# K10P100_V1_0.net
KiCad netlist of a schematic drawn in Altium Designer
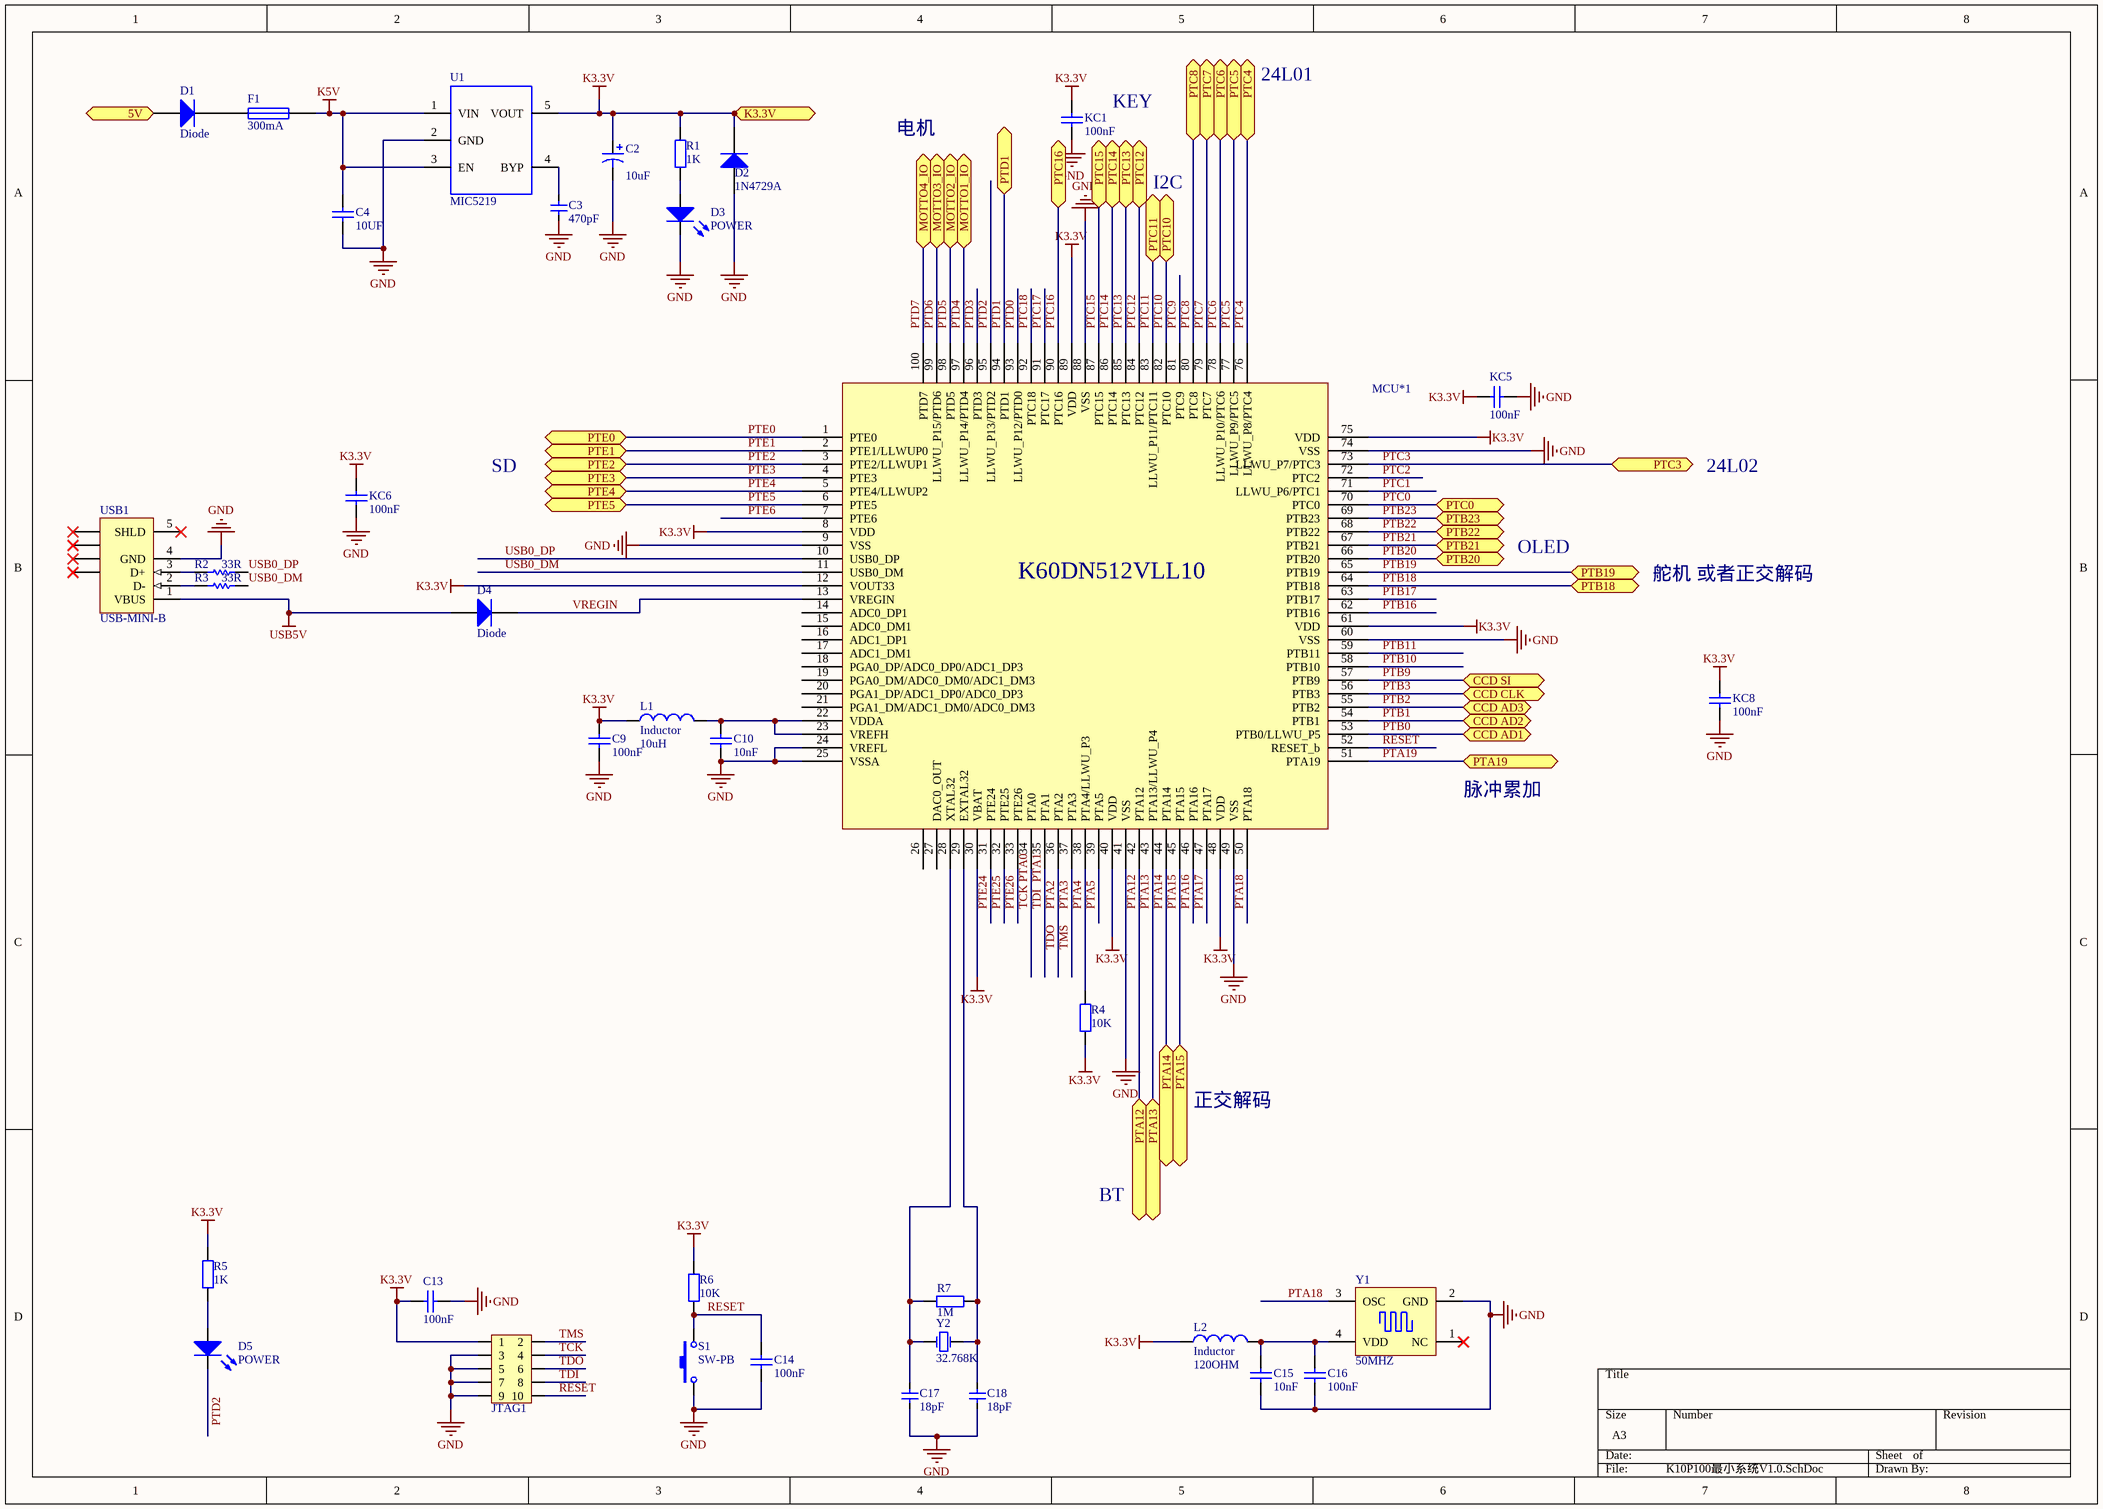
[diagram p0: K10P100最小系统V1.0.SchDoc]

(export (version "E")
  (design (tool "Eeschema 10.0.6"))
  (components
    (comp (ref "C2")
      (value "10uF")
      (footprint "C2012")
      (description "Polarized Capacitor (Radial)")
      (fields (field (name "Comment") "Cap Pol1") (field (name "PUBLISHER") "Altium Limited"))
      (libsource (lib "Miscellaneous Devices") (part "Cap Pol1"))
    )
    (comp (ref "C3")
      (value "470pF")
      (footprint "C2012")
      (description "CAP")
      (libsource (lib "K60-V4.0") (part "陶瓷电容"))
    )
    (comp (ref "C4")
      (value "10UF")
      (footprint "C2012")
      (description "Capacitor")
      (libsource (lib "K60-V4.0") (part "Cap"))
    )
    (comp (ref "C9")
      (value "100nF")
      (footprint "C2012")
      (description "Capacitor")
      (libsource (lib "K60-V4.0") (part "Cap"))
    )
    (comp (ref "C10")
      (value "10nF")
      (footprint "C2012")
      (description "Capacitor")
      (libsource (lib "K60-V4.0") (part "Cap"))
    )
    (comp (ref "C13")
      (value "100nF")
      (footprint "C2012")
      (description "Capacitor")
      (libsource (lib "K60-V4.0") (part "Cap"))
    )
    (comp (ref "C14")
      (value "100nF")
      (footprint "C2012")
      (description "Capacitor")
      (libsource (lib "K60-V4.0") (part "Cap"))
    )
    (comp (ref "C15")
      (value "10nF")
      (footprint "C2012")
      (description "Capacitor")
      (libsource (lib "K60-V4.0") (part "Cap"))
    )
    (comp (ref "C16")
      (value "100nF")
      (footprint "C2012")
      (description "Capacitor")
      (libsource (lib "K60-V4.0") (part "Cap"))
    )
    (comp (ref "C17")
      (value "18pF")
      (footprint "C2012")
      (description "CAP")
      (libsource (lib "K60-V4.0") (part "陶瓷电容"))
    )
    (comp (ref "C18")
      (value "18pF")
      (footprint "C2012")
      (description "CAP")
      (libsource (lib "K60-V4.0") (part "陶瓷电容"))
    )
    (comp (ref "D1")
      (value "Diode")
      (footprint "1206(2)")
      (description "Default Diode")
      (fields (field (name "PUBLISHER") "Altium Limited"))
      (libsource (lib "Miscellaneous Devices") (part "Diode"))
    )
    (comp (ref "D2")
      (value "1N4729A")
      (footprint "C2012")
      (description "High Conductance Fast Diode")
      (fields (field (name "PUBLISHER") "Altium Limited"))
      (libsource (lib "K60-V4.0") (part "Diode 1N4148"))
    )
    (comp (ref "D3")
      (value "POWER")
      (footprint "C2012")
      (description "Typical INFRARED GaAs LED")
      (libsource (lib "K60-V4.0") (part "LED"))
    )
    (comp (ref "D4")
      (value "Diode")
      (footprint "1206(2)")
      (description "Default Diode")
      (fields (field (name "PUBLISHER") "Altium Limited"))
      (libsource (lib "Miscellaneous Devices") (part "Diode"))
    )
    (comp (ref "D5")
      (value "POWER")
      (footprint "C2012")
      (description "Typical INFRARED GaAs LED")
      (libsource (lib "K60-V4.0") (part "LED"))
    )
    (comp (ref "F1")
      (value "300mA")
      (footprint "R2012")
      (description "Fuse")
      (fields (field (name "PUBLISHER") "Altium Limited"))
      (libsource (lib "K60-V4.0") (part "Fuse 1"))
    )
    (comp (ref "JTAG1")
      (value "Header 5X2")
      (footprint "IDC5X2")
      (description "Header, 5-Pin, Dual row")
      (libsource (lib "K60-V4.0") (part "Header 5X2"))
    )
    (comp (ref "KC1")
      (value "100nF")
      (footprint "C2012")
      (description "Capacitor")
      (libsource (lib "K60-V4.0") (part "Cap"))
    )
    (comp (ref "KC5")
      (value "100nF")
      (footprint "C2012")
      (description "Capacitor")
      (libsource (lib "K60-V4.0") (part "Cap"))
    )
    (comp (ref "KC6")
      (value "100nF")
      (footprint "C2012")
      (description "Capacitor")
      (libsource (lib "K60-V4.0") (part "Cap"))
    )
    (comp (ref "KC8")
      (value "100nF")
      (footprint "C2012")
      (description "Capacitor")
      (libsource (lib "K60-V4.0") (part "Cap"))
    )
    (comp (ref "L1")
      (value "Inductor")
      (footprint "C2012")
      (fields (field (name "ALTIUM_VALUE") "10uH") (field (name "PUBLISHER") "Altium Limited"))
      (libsource (lib "Miscellaneous Devices") (part "Inductor"))
    )
    (comp (ref "L2")
      (value "Inductor")
      (footprint "C2012")
      (fields (field (name "ALTIUM_VALUE") "120OHM") (field (name "PUBLISHER") "Altium Limited"))
      (libsource (lib "Miscellaneous Devices") (part "Inductor"))
    )
    (comp (ref "MCU*1") (value "k60P100") (footprint "LQFP100") (libsource (lib "原理图") (part "k60P100")))
    (comp (ref "R1")
      (value "1K")
      (footprint "R2012")
      (description "Resistor of led")
      (libsource (lib "") (part "Res_1"))
    )
    (comp (ref "R2")
      (value "33R")
      (footprint "R2012")
      (description "贴片电阻")
      (fields (field (name "PUBLISHER") "Altium Limited"))
      (libsource (lib "Sparks") (part "Res"))
    )
    (comp (ref "R3")
      (value "33R")
      (footprint "R2012")
      (description "贴片电阻")
      (fields (field (name "PUBLISHER") "Altium Limited"))
      (libsource (lib "Sparks") (part "Res"))
    )
    (comp (ref "R4")
      (value "10K")
      (footprint "R2012")
      (description "Resistor of led")
      (libsource (lib "") (part "Res_1"))
    )
    (comp (ref "R5")
      (value "1K")
      (footprint "R2012")
      (description "Resistor of led")
      (libsource (lib "") (part "Res_1"))
    )
    (comp (ref "R6")
      (value "10K")
      (footprint "R2012")
      (description "Resistor")
      (libsource (lib "") (part "Res_1"))
    )
    (comp (ref "R7")
      (value "1M")
      (footprint "R2012")
      (description "Resistor")
      (libsource (lib "K60-V4.0") (part "Res"))
    )
    (comp (ref "S1")
      (value "SW-PB")
      (footprint "sw 3*4 *2")
      (description "Switch")
      (libsource (lib "K60-V4.0") (part "SW-PB"))
    )
    (comp (ref "U1")
      (value "MIC5219")
      (footprint "SOT-23-5")
      (description "LDO")
      (libsource (lib "K60-V4.0") (part "MIC5219"))
    )
    (comp (ref "USB1")
      (value "USB-MINI-B")
      (footprint "USB-MINI-B")
      (description "USB 2.0, Right Angle, SMT, A Type, Receptacle, 5 Position, Black")
      (fields (field (name "PUBLISHER") "Altium Limited"))
      (libsource (lib "Sparks") (part "USB-MINI-B"))
    )
    (comp (ref "Y1") (value "50MHZ") (footprint "贴片有源晶体") (libsource (lib "K60-V4.0") (part "XTAL1")))
    (comp (ref "Y2")
      (value "32.768K")
      (footprint "CT3215")
      (description "Crystal Oscillator")
      (libsource (lib "K60-V4.0") (part "XTAL"))
    )
  )
  (nets
    (net (code "1") (name "/5V") (class "Default")
      (node (ref "D1") (pin "1") (pinfunction "A_1") (pintype "passive"))
    )
    (net (code "2") (name "/PTA0") (class "Default")
      (node (ref "JTAG1") (pin "4") (pinfunction "4_4") (pintype "passive"))
      (node (ref "MCU*1") (pin "34") (pinfunction "PTA0_34") (pintype "passive"))
    )
    (net (code "3") (name "/PTA1") (class "Default")
      (node (ref "JTAG1") (pin "8") (pinfunction "8_8") (pintype "passive"))
      (node (ref "MCU*1") (pin "35") (pinfunction "PTA1_35") (pintype "passive"))
    )
    (net (code "4") (name "/PTA2") (class "Default")
      (node (ref "JTAG1") (pin "6") (pinfunction "6_6") (pintype "passive"))
      (node (ref "MCU*1") (pin "36") (pinfunction "PTA2_36") (pintype "passive"))
    )
    (net (code "5") (name "/PTA3") (class "Default")
      (node (ref "JTAG1") (pin "2") (pinfunction "2_2") (pintype "passive"))
      (node (ref "MCU*1") (pin "37") (pinfunction "PTA3_37") (pintype "passive"))
    )
    (net (code "6") (name "/PTA4") (class "Default")
      (node (ref "MCU*1") (pin "38") (pinfunction "PTA4/LLWU_P3_38") (pintype "passive"))
      (node (ref "R4") (pin "2") (pinfunction "2_2") (pintype "passive"))
    )
    (net (code "7") (name "/PTA5") (class "Default")
      (node (ref "MCU*1") (pin "39") (pinfunction "PTA5_39") (pintype "passive"))
    )
    (net (code "8") (name "/PTA12") (class "Default")
      (node (ref "MCU*1") (pin "42") (pinfunction "PTA12_42") (pintype "passive"))
    )
    (net (code "9") (name "/PTA13") (class "Default")
      (node (ref "MCU*1") (pin "43") (pinfunction "PTA13/LLWU_P4_43") (pintype "passive"))
    )
    (net (code "10") (name "/PTA14") (class "Default")
      (node (ref "MCU*1") (pin "44") (pinfunction "PTA14_44") (pintype "passive"))
    )
    (net (code "11") (name "/PTA15") (class "Default")
      (node (ref "MCU*1") (pin "45") (pinfunction "PTA15_45") (pintype "passive"))
    )
    (net (code "12") (name "/PTA16") (class "Default")
      (node (ref "MCU*1") (pin "46") (pinfunction "PTA16_46") (pintype "passive"))
    )
    (net (code "13") (name "/PTA17") (class "Default")
      (node (ref "MCU*1") (pin "47") (pinfunction "PTA17_47") (pintype "passive"))
    )
    (net (code "14") (name "/PTA18") (class "Default")
      (node (ref "MCU*1") (pin "50") (pinfunction "PTA18_50") (pintype "passive"))
      (node (ref "Y1") (pin "3") (pinfunction "OSC_3") (pintype "passive"))
    )
    (net (code "15") (name "/PTA19") (class "Default")
      (node (ref "MCU*1") (pin "51") (pinfunction "PTA19_51") (pintype "passive"))
    )
    (net (code "16") (name "/PTB0") (class "Default")
      (node (ref "MCU*1") (pin "53") (pinfunction "PTB0/LLWU_P5_53") (pintype "passive"))
    )
    (net (code "17") (name "/PTB1") (class "Default")
      (node (ref "MCU*1") (pin "54") (pinfunction "PTB1_54") (pintype "passive"))
    )
    (net (code "18") (name "/PTB2") (class "Default")
      (node (ref "MCU*1") (pin "55") (pinfunction "PTB2_55") (pintype "passive"))
    )
    (net (code "19") (name "/PTB3") (class "Default")
      (node (ref "MCU*1") (pin "56") (pinfunction "PTB3_56") (pintype "passive"))
    )
    (net (code "20") (name "/PTB9") (class "Default")
      (node (ref "MCU*1") (pin "57") (pinfunction "PTB9_57") (pintype "passive"))
    )
    (net (code "21") (name "/PTB10") (class "Default")
      (node (ref "MCU*1") (pin "58") (pinfunction "PTB10_58") (pintype "passive"))
    )
    (net (code "22") (name "/PTB11") (class "Default")
      (node (ref "MCU*1") (pin "59") (pinfunction "PTB11_59") (pintype "passive"))
    )
    (net (code "23") (name "/PTB16") (class "Default")
      (node (ref "MCU*1") (pin "62") (pinfunction "PTB16_62") (pintype "passive"))
    )
    (net (code "24") (name "/PTB17") (class "Default")
      (node (ref "MCU*1") (pin "63") (pinfunction "PTB17_63") (pintype "passive"))
    )
    (net (code "25") (name "/PTB18") (class "Default")
      (node (ref "MCU*1") (pin "64") (pinfunction "PTB18_64") (pintype "passive"))
    )
    (net (code "26") (name "/PTB19") (class "Default")
      (node (ref "MCU*1") (pin "65") (pinfunction "PTB19_65") (pintype "passive"))
    )
    (net (code "27") (name "/PTB20") (class "Default")
      (node (ref "MCU*1") (pin "66") (pinfunction "PTB20_66") (pintype "passive"))
    )
    (net (code "28") (name "/PTB21") (class "Default")
      (node (ref "MCU*1") (pin "67") (pinfunction "PTB21_67") (pintype "passive"))
    )
    (net (code "29") (name "/PTB22") (class "Default")
      (node (ref "MCU*1") (pin "68") (pinfunction "PTB22_68") (pintype "passive"))
    )
    (net (code "30") (name "/PTB23") (class "Default")
      (node (ref "MCU*1") (pin "69") (pinfunction "PTB23_69") (pintype "passive"))
    )
    (net (code "31") (name "/PTC0") (class "Default")
      (node (ref "MCU*1") (pin "70") (pinfunction "PTC0_70") (pintype "passive"))
    )
    (net (code "32") (name "/PTC1") (class "Default")
      (node (ref "MCU*1") (pin "71") (pinfunction "LLWU_P6/PTC1_71") (pintype "passive"))
    )
    (net (code "33") (name "/PTC2") (class "Default")
      (node (ref "MCU*1") (pin "72") (pinfunction "PTC2_72") (pintype "passive"))
    )
    (net (code "34") (name "/PTC3") (class "Default")
      (node (ref "MCU*1") (pin "73") (pinfunction "LLWU_P7/PTC3_73") (pintype "passive"))
    )
    (net (code "35") (name "/PTC4") (class "Default")
      (node (ref "MCU*1") (pin "76") (pinfunction "LLWU_P8/PTC4_76") (pintype "passive"))
    )
    (net (code "36") (name "/PTC5") (class "Default")
      (node (ref "MCU*1") (pin "77") (pinfunction "LLWU_P9/PTC5_77") (pintype "passive"))
    )
    (net (code "37") (name "/PTC6") (class "Default")
      (node (ref "MCU*1") (pin "78") (pinfunction "LLWU_P10/PTC6_78") (pintype "passive"))
    )
    (net (code "38") (name "/PTC7") (class "Default")
      (node (ref "MCU*1") (pin "79") (pinfunction "PTC7_79") (pintype "passive"))
    )
    (net (code "39") (name "/PTC8") (class "Default")
      (node (ref "MCU*1") (pin "80") (pinfunction "PTC8_80") (pintype "passive"))
    )
    (net (code "40") (name "/PTC9") (class "Default")
      (node (ref "MCU*1") (pin "81") (pinfunction "PTC9_81") (pintype "passive"))
    )
    (net (code "41") (name "/PTC10") (class "Default")
      (node (ref "MCU*1") (pin "82") (pinfunction "PTC10_82") (pintype "passive"))
    )
    (net (code "42") (name "/PTC11") (class "Default")
      (node (ref "MCU*1") (pin "83") (pinfunction "LLWU_P11/PTC11_83") (pintype "passive"))
    )
    (net (code "43") (name "/PTC12") (class "Default")
      (node (ref "MCU*1") (pin "84") (pinfunction "PTC12_84") (pintype "passive"))
    )
    (net (code "44") (name "/PTC13") (class "Default")
      (node (ref "MCU*1") (pin "85") (pinfunction "PTC13_85") (pintype "passive"))
    )
    (net (code "45") (name "/PTC14") (class "Default")
      (node (ref "MCU*1") (pin "86") (pinfunction "PTC14_86") (pintype "passive"))
    )
    (net (code "46") (name "/PTC15") (class "Default")
      (node (ref "MCU*1") (pin "87") (pinfunction "PTC15_87") (pintype "passive"))
    )
    (net (code "47") (name "/PTC16") (class "Default")
      (node (ref "MCU*1") (pin "90") (pinfunction "PTC16_90") (pintype "passive"))
    )
    (net (code "48") (name "/PTC17") (class "Default")
      (node (ref "MCU*1") (pin "91") (pinfunction "PTC17_91") (pintype "passive"))
    )
    (net (code "49") (name "/PTC18") (class "Default")
      (node (ref "MCU*1") (pin "92") (pinfunction "PTC18_92") (pintype "passive"))
    )
    (net (code "50") (name "/PTD0") (class "Default")
      (node (ref "MCU*1") (pin "93") (pinfunction "LLWU_P12/PTD0_93") (pintype "passive"))
    )
    (net (code "51") (name "/PTD1") (class "Default")
      (node (ref "MCU*1") (pin "94") (pinfunction "PTD1_94") (pintype "passive"))
    )
    (net (code "52") (name "/PTD2") (class "Default")
      (node (ref "D5") (pin "2") (pinfunction "2_2") (pintype "passive"))
      (node (ref "MCU*1") (pin "95") (pinfunction "LLWU_P13/PTD2_95") (pintype "passive"))
    )
    (net (code "53") (name "/PTD3") (class "Default")
      (node (ref "MCU*1") (pin "96") (pinfunction "PTD3_96") (pintype "passive"))
    )
    (net (code "54") (name "/PTD4") (class "Default")
      (node (ref "MCU*1") (pin "97") (pinfunction "LLWU_P14/PTD4_97") (pintype "passive"))
    )
    (net (code "55") (name "/PTD5") (class "Default")
      (node (ref "MCU*1") (pin "98") (pinfunction "PTD5_98") (pintype "passive"))
    )
    (net (code "56") (name "/PTD6") (class "Default")
      (node (ref "MCU*1") (pin "99") (pinfunction "LLWU_P15/PTD6_99") (pintype "passive"))
    )
    (net (code "57") (name "/PTD7") (class "Default")
      (node (ref "MCU*1") (pin "100") (pinfunction "PTD7_100") (pintype "passive"))
    )
    (net (code "58") (name "/PTE0") (class "Default")
      (node (ref "MCU*1") (pin "1") (pinfunction "PTE0_1") (pintype "passive"))
    )
    (net (code "59") (name "/PTE1") (class "Default")
      (node (ref "MCU*1") (pin "2") (pinfunction "PTE1/LLWUP0_2") (pintype "passive"))
    )
    (net (code "60") (name "/PTE2") (class "Default")
      (node (ref "MCU*1") (pin "3") (pinfunction "PTE2/LLWUP1_3") (pintype "passive"))
    )
    (net (code "61") (name "/PTE3") (class "Default")
      (node (ref "MCU*1") (pin "4") (pinfunction "PTE3_4") (pintype "passive"))
    )
    (net (code "62") (name "/PTE4") (class "Default")
      (node (ref "MCU*1") (pin "5") (pinfunction "PTE4/LLWUP2_5") (pintype "passive"))
    )
    (net (code "63") (name "/PTE5") (class "Default")
      (node (ref "MCU*1") (pin "6") (pinfunction "PTE5_6") (pintype "passive"))
    )
    (net (code "64") (name "/PTE6") (class "Default")
      (node (ref "MCU*1") (pin "7") (pinfunction "PTE6_7") (pintype "passive"))
    )
    (net (code "65") (name "/PTE24") (class "Default")
      (node (ref "MCU*1") (pin "31") (pinfunction "PTE24_31") (pintype "passive"))
    )
    (net (code "66") (name "/PTE25") (class "Default")
      (node (ref "MCU*1") (pin "32") (pinfunction "PTE25_32") (pintype "passive"))
    )
    (net (code "67") (name "/PTE26") (class "Default")
      (node (ref "MCU*1") (pin "33") (pinfunction "PTE26_33") (pintype "passive"))
    )
    (net (code "68") (name "/RESET") (class "Default")
      (node (ref "C14") (pin "2") (pinfunction "2_2") (pintype "passive"))
      (node (ref "JTAG1") (pin "10") (pinfunction "10_10") (pintype "passive"))
      (node (ref "MCU*1") (pin "52") (pinfunction "RESET_b_52") (pintype "passive"))
      (node (ref "R6") (pin "1") (pinfunction "1_1") (pintype "passive"))
      (node (ref "S1") (pin "2") (pinfunction "2_2") (pintype "passive"))
    )
    (net (code "69") (name "/USB0_DM") (class "Default")
      (node (ref "MCU*1") (pin "11") (pinfunction "USB0_DM_11") (pintype "passive"))
      (node (ref "R3") (pin "2") (pinfunction "2_2") (pintype "passive"))
    )
    (net (code "70") (name "/USB0_DP") (class "Default")
      (node (ref "MCU*1") (pin "10") (pinfunction "USB0_DP_10") (pintype "passive"))
      (node (ref "R2") (pin "2") (pinfunction "2_2") (pintype "passive"))
    )
    (net (code "71") (name "/VREGIN") (class "Default")
      (node (ref "D4") (pin "2") (pinfunction "K_2") (pintype "passive"))
      (node (ref "MCU*1") (pin "13") (pinfunction "VREGIN_13") (pintype "passive"))
    )
    (net (code "72") (name "GND") (class "Default")
      (node (ref "C10") (pin "1") (pinfunction "1_1") (pintype "passive"))
      (node (ref "C13") (pin "2") (pinfunction "2_2") (pintype "passive"))
      (node (ref "C14") (pin "1") (pinfunction "1_1") (pintype "passive"))
      (node (ref "C15") (pin "1") (pinfunction "1_1") (pintype "passive"))
      (node (ref "C16") (pin "1") (pinfunction "1_1") (pintype "passive"))
      (node (ref "C17") (pin "1") (pinfunction "1_1") (pintype "passive"))
      (node (ref "C18") (pin "1") (pinfunction "1_1") (pintype "passive"))
      (node (ref "C2") (pin "2") (pinfunction "2_2") (pintype "passive"))
      (node (ref "C3") (pin "1") (pinfunction "1_1") (pintype "passive"))
      (node (ref "C4") (pin "1") (pinfunction "1_1") (pintype "passive"))
      (node (ref "C9") (pin "1") (pinfunction "1_1") (pintype "passive"))
      (node (ref "D2") (pin "1") (pinfunction "A_1") (pintype "passive"))
      (node (ref "D3") (pin "2") (pinfunction "2_2") (pintype "passive"))
      (node (ref "JTAG1") (pin "3") (pinfunction "3_3") (pintype "passive"))
      (node (ref "JTAG1") (pin "5") (pinfunction "5_5") (pintype "passive"))
      (node (ref "JTAG1") (pin "7") (pinfunction "7_7") (pintype "passive"))
      (node (ref "JTAG1") (pin "9") (pinfunction "9_9") (pintype "passive"))
      (node (ref "KC1") (pin "1") (pinfunction "1_1") (pintype "passive"))
      (node (ref "KC5") (pin "1") (pinfunction "1_1") (pintype "passive"))
      (node (ref "KC6") (pin "1") (pinfunction "1_1") (pintype "passive"))
      (node (ref "KC8") (pin "1") (pinfunction "1_1") (pintype "passive"))
      (node (ref "MCU*1") (pin "24") (pinfunction "VREFL_24") (pintype "passive"))
      (node (ref "MCU*1") (pin "25") (pinfunction "VSSA_25") (pintype "passive"))
      (node (ref "MCU*1") (pin "41") (pinfunction "VSS_41") (pintype "passive"))
      (node (ref "MCU*1") (pin "49") (pinfunction "VSS_49") (pintype "passive"))
      (node (ref "MCU*1") (pin "60") (pinfunction "VSS_60") (pintype "passive"))
      (node (ref "MCU*1") (pin "74") (pinfunction "VSS_74") (pintype "passive"))
      (node (ref "MCU*1") (pin "88") (pinfunction "VSS_88") (pintype "passive"))
      (node (ref "MCU*1") (pin "9") (pinfunction "VSS_9") (pintype "passive"))
      (node (ref "S1") (pin "1") (pinfunction "1_1") (pintype "passive"))
      (node (ref "U1") (pin "2") (pinfunction "GND_2") (pintype "passive"))
      (node (ref "USB1") (pin "4") (pinfunction "GND_4") (pintype "power_in"))
      (node (ref "Y1") (pin "2") (pinfunction "GND_2") (pintype "passive"))
    )
    (net (code "73") (name "K3.3V") (class "Default")
      (node (ref "C13") (pin "1") (pinfunction "1_1") (pintype "passive"))
      (node (ref "C2") (pin "1") (pinfunction "1_1") (pintype "passive"))
      (node (ref "C9") (pin "2") (pinfunction "2_2") (pintype "passive"))
      (node (ref "D2") (pin "2") (pinfunction "K_2") (pintype "passive"))
      (node (ref "JTAG1") (pin "1") (pinfunction "1_1") (pintype "passive"))
      (node (ref "KC1") (pin "2") (pinfunction "2_2") (pintype "passive"))
      (node (ref "KC5") (pin "2") (pinfunction "2_2") (pintype "passive"))
      (node (ref "KC6") (pin "2") (pinfunction "2_2") (pintype "passive"))
      (node (ref "KC8") (pin "2") (pinfunction "2_2") (pintype "passive"))
      (node (ref "L1") (pin "1") (pinfunction "1_1") (pintype "passive"))
      (node (ref "L2") (pin "1") (pinfunction "1_1") (pintype "passive"))
      (node (ref "MCU*1") (pin "12") (pinfunction "VOUT33_12") (pintype "passive"))
      (node (ref "MCU*1") (pin "30") (pinfunction "VBAT_30") (pintype "passive"))
      (node (ref "MCU*1") (pin "40") (pinfunction "VDD_40") (pintype "passive"))
      (node (ref "MCU*1") (pin "48") (pinfunction "VDD_48") (pintype "passive"))
      (node (ref "MCU*1") (pin "61") (pinfunction "VDD_61") (pintype "passive"))
      (node (ref "MCU*1") (pin "75") (pinfunction "VDD_75") (pintype "passive"))
      (node (ref "MCU*1") (pin "8") (pinfunction "VDD_8") (pintype "passive"))
      (node (ref "MCU*1") (pin "89") (pinfunction "VDD_89") (pintype "passive"))
      (node (ref "R1") (pin "2") (pinfunction "2_2") (pintype "passive"))
      (node (ref "R4") (pin "1") (pinfunction "1_1") (pintype "passive"))
      (node (ref "R5") (pin "2") (pinfunction "2_2") (pintype "passive"))
      (node (ref "R6") (pin "2") (pinfunction "2_2") (pintype "passive"))
      (node (ref "U1") (pin "5") (pinfunction "VOUT_5") (pintype "passive"))
    )
    (net (code "74") (name "K5V") (class "Default")
      (node (ref "C4") (pin "2") (pinfunction "2_2") (pintype "passive"))
      (node (ref "F1") (pin "1") (pinfunction "1_1") (pintype "passive"))
      (node (ref "U1") (pin "1") (pinfunction "VIN_1") (pintype "passive"))
      (node (ref "U1") (pin "3") (pinfunction "EN_3") (pintype "passive"))
    )
    (net (code "75") (name "Net-(D1-K)") (class "Default")
      (node (ref "D1") (pin "2") (pinfunction "K_2") (pintype "passive"))
      (node (ref "F1") (pin "2") (pinfunction "2_2") (pintype "passive"))
    )
    (net (code "76") (name "Net-(D3-Pad1)") (class "Default")
      (node (ref "D3") (pin "1") (pinfunction "1_1") (pintype "passive"))
      (node (ref "R1") (pin "1") (pinfunction "1_1") (pintype "passive"))
    )
    (net (code "77") (name "Net-(D5-Pad1)") (class "Default")
      (node (ref "D5") (pin "1") (pinfunction "1_1") (pintype "passive"))
      (node (ref "R5") (pin "1") (pinfunction "1_1") (pintype "passive"))
    )
    (net (code "78") (name "Net-(MCU*1-EXTAL32)") (class "Default")
      (node (ref "C18") (pin "2") (pinfunction "2_2") (pintype "passive"))
      (node (ref "MCU*1") (pin "29") (pinfunction "EXTAL32_29") (pintype "passive"))
      (node (ref "R7") (pin "2") (pinfunction "2_2") (pintype "passive"))
      (node (ref "Y2") (pin "2") (pinfunction "OSC2_2") (pintype "passive"))
    )
    (net (code "79") (name "Net-(MCU*1-VDDA)") (class "Default")
      (node (ref "C10") (pin "2") (pinfunction "2_2") (pintype "passive"))
      (node (ref "L1") (pin "2") (pinfunction "2_2") (pintype "passive"))
      (node (ref "MCU*1") (pin "22") (pinfunction "VDDA_22") (pintype "passive"))
      (node (ref "MCU*1") (pin "23") (pinfunction "VREFH_23") (pintype "passive"))
    )
    (net (code "80") (name "Net-(MCU*1-XTAL32)") (class "Default")
      (node (ref "C17") (pin "2") (pinfunction "2_2") (pintype "passive"))
      (node (ref "MCU*1") (pin "28") (pinfunction "XTAL32_28") (pintype "passive"))
      (node (ref "R7") (pin "1") (pinfunction "1_1") (pintype "passive"))
      (node (ref "Y2") (pin "1") (pinfunction "OSC1_1") (pintype "passive"))
    )
    (net (code "81") (name "Net-(U1-BYP)") (class "Default")
      (node (ref "C3") (pin "2") (pinfunction "2_2") (pintype "passive"))
      (node (ref "U1") (pin "4") (pinfunction "BYP_4") (pintype "passive"))
    )
    (net (code "82") (name "Net-(USB1-D+)") (class "Default")
      (node (ref "R2") (pin "1") (pinfunction "1_1") (pintype "passive"))
      (node (ref "USB1") (pin "3") (pinfunction "D+_3") (pintype "input"))
    )
    (net (code "83") (name "Net-(USB1-D-)") (class "Default")
      (node (ref "R3") (pin "1") (pinfunction "1_1") (pintype "passive"))
      (node (ref "USB1") (pin "2") (pinfunction "D-_2") (pintype "input"))
    )
    (net (code "84") (name "Net-(Y1-VDD)") (class "Default")
      (node (ref "C15") (pin "2") (pinfunction "2_2") (pintype "passive"))
      (node (ref "C16") (pin "2") (pinfunction "2_2") (pintype "passive"))
      (node (ref "L2") (pin "2") (pinfunction "2_2") (pintype "passive"))
      (node (ref "Y1") (pin "4") (pinfunction "VDD_4") (pintype "passive"))
    )
    (net (code "85") (name "USB5V") (class "Default")
      (node (ref "D4") (pin "1") (pinfunction "A_1") (pintype "passive"))
      (node (ref "USB1") (pin "1") (pinfunction "VBUS_1") (pintype "power_in"))
    )
    (net (code "86") (name "unconnected-(MCU*1-ADC0_DM1-Pad15)") (class "Default")
      (node (ref "MCU*1") (pin "15") (pinfunction "ADC0_DM1_15") (pintype "passive"))
    )
    (net (code "87") (name "unconnected-(MCU*1-ADC0_DP1-Pad14)") (class "Default")
      (node (ref "MCU*1") (pin "14") (pinfunction "ADC0_DP1_14") (pintype "passive"))
    )
    (net (code "88") (name "unconnected-(MCU*1-ADC1_DM1-Pad17)") (class "Default")
      (node (ref "MCU*1") (pin "17") (pinfunction "ADC1_DM1_17") (pintype "passive"))
    )
    (net (code "89") (name "unconnected-(MCU*1-ADC1_DP1-Pad16)") (class "Default")
      (node (ref "MCU*1") (pin "16") (pinfunction "ADC1_DP1_16") (pintype "passive"))
    )
    (net (code "90") (name "unconnected-(MCU*1-DAC0_OUT-Pad27)") (class "Default")
      (node (ref "MCU*1") (pin "27") (pinfunction "DAC0_OUT_27") (pintype "passive"))
    )
    (net (code "91") (name "unconnected-(MCU*1-PGA0_DM{slash}ADC0_DM0{slash}ADC1_DM3-Pad19)") (class "Default")
      (node (ref "MCU*1") (pin "19") (pinfunction "PGA0_DM/ADC0_DM0/ADC1_DM3_19") (pintype "passive"))
    )
    (net (code "92") (name "unconnected-(MCU*1-PGA0_DP{slash}ADC0_DP0{slash}ADC1_DP3-Pad18)") (class "Default")
      (node (ref "MCU*1") (pin "18") (pinfunction "PGA0_DP/ADC0_DP0/ADC1_DP3_18") (pintype "passive"))
    )
    (net (code "93") (name "unconnected-(MCU*1-PGA1_DM{slash}ADC1_DM0{slash}ADC0_DM3-Pad21)") (class "Default")
      (node (ref "MCU*1") (pin "21") (pinfunction "PGA1_DM/ADC1_DM0/ADC0_DM3_21") (pintype "passive"))
    )
    (net (code "94") (name "unconnected-(MCU*1-PGA1_DP{slash}ADC1_DP0{slash}ADC0_DP3-Pad20)") (class "Default")
      (node (ref "MCU*1") (pin "20") (pinfunction "PGA1_DP/ADC1_DP0/ADC0_DP3_20") (pintype "passive"))
    )
    (net (code "95") (name "unconnected-(MCU*1-VREF_OUT{slash}CMP1_IN5CMP0_IN5{slash}ADC1_SE18-Pad26)") (class "Default")
      (node (ref "MCU*1") (pin "26") (pinfunction "VREF_OUT/CMP1_IN5CMP0_IN5/ADC1_SE18_26") (pintype "passive"))
    )
    (net (code "96") (name "unconnected-(USB1-SHLD-Pad5)") (class "Default")
      (node (ref "USB1") (pin "5") (pinfunction "SHLD_5") (pintype "passive+no_connect"))
    )
    (net (code "97") (name "unconnected-(USB1-SHLD-Pad6)") (class "Default")
      (node (ref "USB1") (pin "6") (pinfunction "SHLD_6") (pintype "passive+no_connect"))
    )
    (net (code "98") (name "unconnected-(USB1-SHLD-Pad7)") (class "Default")
      (node (ref "USB1") (pin "7") (pinfunction "SHLD_7") (pintype "passive+no_connect"))
    )
    (net (code "99") (name "unconnected-(USB1-SHLD-Pad8)") (class "Default")
      (node (ref "USB1") (pin "8") (pinfunction "SHLD_8") (pintype "passive+no_connect"))
    )
    (net (code "100") (name "unconnected-(USB1-SHLD-Pad9)") (class "Default")
      (node (ref "USB1") (pin "9") (pinfunction "SHLD_9") (pintype "passive+no_connect"))
    )
    (net (code "101") (name "unconnected-(Y1-NC-Pad1)") (class "Default")
      (node (ref "Y1") (pin "1") (pinfunction "NC_1") (pintype "passive+no_connect"))
    )
  )
)
